# shrg-001.net
KiCad netlist of a schematic drawn in EAGLE
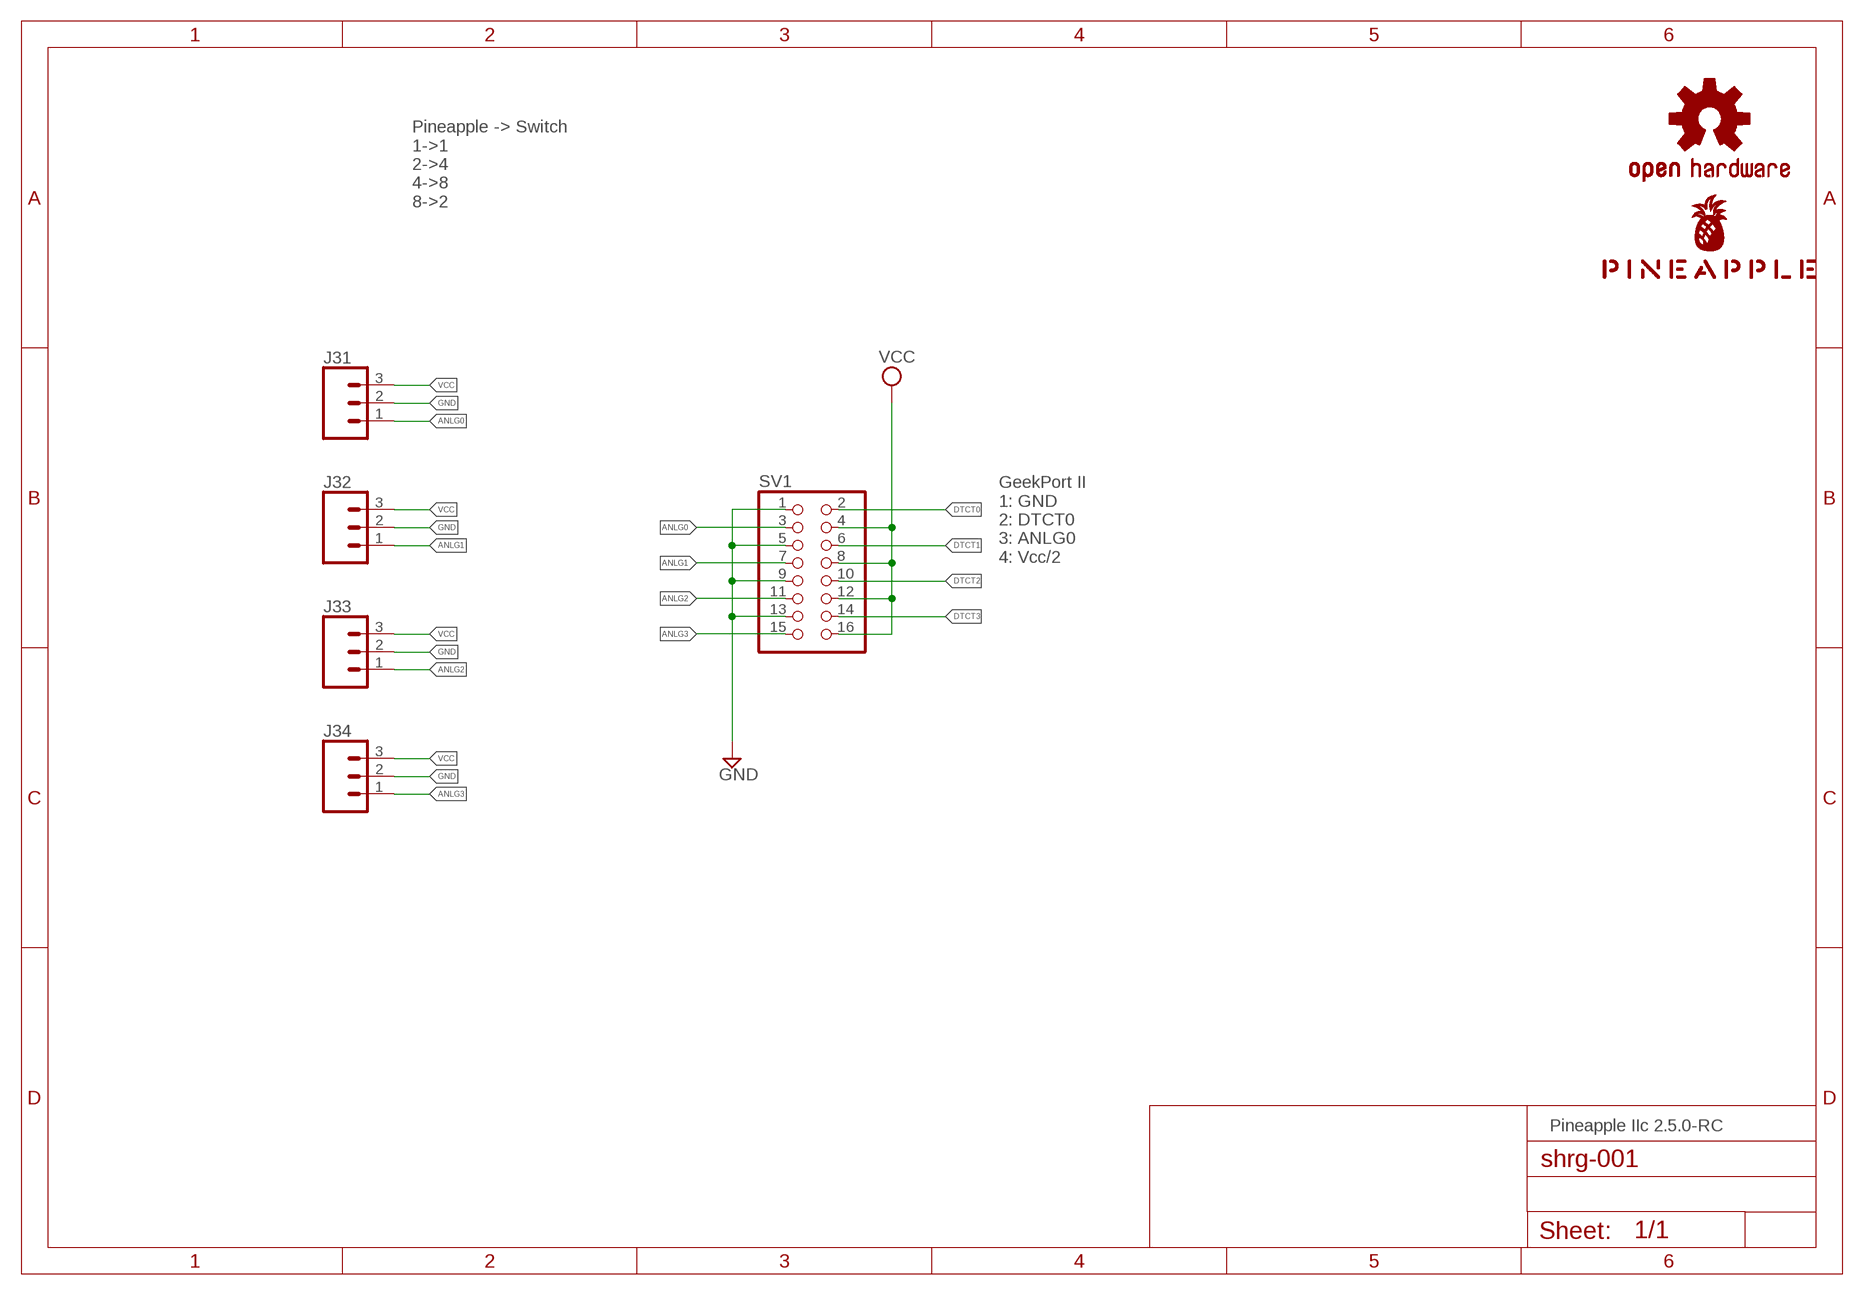
[diagram p0: schematic, sheet 1]

(export (version "E")
  (design (tool "Eeschema 10.0.6"))
  (components
    (comp (ref "J31")
      (value "CONN_03JST-PTH-VERT")
      (footprint "eagle-import:JST-3-PTH-VERT")
      (libsource (lib "eagle-import") (part "CONN_03JST-PTH-VERT"))
    )
    (comp (ref "J32")
      (value "CONN_03JST-PTH-VERT")
      (footprint "eagle-import:JST-3-PTH-VERT")
      (libsource (lib "eagle-import") (part "CONN_03JST-PTH-VERT"))
    )
    (comp (ref "J33")
      (value "CONN_03JST-PTH-VERT")
      (footprint "eagle-import:JST-3-PTH-VERT")
      (libsource (lib "eagle-import") (part "CONN_03JST-PTH-VERT"))
    )
    (comp (ref "J34")
      (value "CONN_03JST-PTH-VERT")
      (footprint "eagle-import:JST-3-PTH-VERT")
      (libsource (lib "eagle-import") (part "CONN_03JST-PTH-VERT"))
    )
    (comp (ref "LOGO1")
      (value "OSHW-LOGOS-COPPER")
      (footprint "eagle-import:OSHW-LOGO-S_COPPER")
      (libsource (lib "eagle-import") (part "OSHW-LOGOS-COPPER"))
    )
    (comp (ref "SV1")
      (value "PINHD-2X8")
      (footprint "eagle-import:2X08")
      (libsource (lib "eagle-import") (part "PINHD-2X8"))
    )
    (comp (ref "U$1")
      (value "PINEAPPLE450_SILK")
      (footprint "eagle-import:PINEAPPLE450_SILK")
      (libsource (lib "eagle-import") (part "PINEAPPLE450_SILK"))
    )
  )
  (nets
    (net (code "1") (name "ANLG0") (class "Default")
      (node (ref "J31") (pin "1") (pinfunction "1_1") (pintype "passive"))
      (node (ref "SV1") (pin "3") (pinfunction "3_3") (pintype "passive"))
    )
    (net (code "2") (name "ANLG1") (class "Default")
      (node (ref "J32") (pin "1") (pinfunction "1_1") (pintype "passive"))
      (node (ref "SV1") (pin "7") (pinfunction "7_7") (pintype "passive"))
    )
    (net (code "3") (name "ANLG2") (class "Default")
      (node (ref "J33") (pin "1") (pinfunction "1_1") (pintype "passive"))
      (node (ref "SV1") (pin "11") (pinfunction "11_11") (pintype "passive"))
    )
    (net (code "4") (name "ANLG3") (class "Default")
      (node (ref "J34") (pin "1") (pinfunction "1_1") (pintype "passive"))
      (node (ref "SV1") (pin "15") (pinfunction "15_15") (pintype "passive"))
    )
    (net (code "5") (name "DTCT0") (class "Default")
      (node (ref "SV1") (pin "2") (pinfunction "2_2") (pintype "passive"))
    )
    (net (code "6") (name "DTCT1") (class "Default")
      (node (ref "SV1") (pin "6") (pinfunction "6_6") (pintype "passive"))
    )
    (net (code "7") (name "DTCT2") (class "Default")
      (node (ref "SV1") (pin "10") (pinfunction "10_10") (pintype "passive"))
    )
    (net (code "8") (name "DTCT3") (class "Default")
      (node (ref "SV1") (pin "14") (pinfunction "14_14") (pintype "passive"))
    )
    (net (code "9") (name "GND") (class "Default")
      (node (ref "J31") (pin "2") (pinfunction "2_2") (pintype "passive"))
      (node (ref "J32") (pin "2") (pinfunction "2_2") (pintype "passive"))
      (node (ref "J33") (pin "2") (pinfunction "2_2") (pintype "passive"))
      (node (ref "J34") (pin "2") (pinfunction "2_2") (pintype "passive"))
      (node (ref "SV1") (pin "1") (pinfunction "1_1") (pintype "passive"))
      (node (ref "SV1") (pin "13") (pinfunction "13_13") (pintype "passive"))
      (node (ref "SV1") (pin "5") (pinfunction "5_5") (pintype "passive"))
      (node (ref "SV1") (pin "9") (pinfunction "9_9") (pintype "passive"))
    )
    (net (code "10") (name "VCC") (class "Default")
      (node (ref "J31") (pin "3") (pinfunction "3_3") (pintype "passive"))
      (node (ref "J32") (pin "3") (pinfunction "3_3") (pintype "passive"))
      (node (ref "J33") (pin "3") (pinfunction "3_3") (pintype "passive"))
      (node (ref "J34") (pin "3") (pinfunction "3_3") (pintype "passive"))
      (node (ref "SV1") (pin "12") (pinfunction "12_12") (pintype "passive"))
      (node (ref "SV1") (pin "16") (pinfunction "16_16") (pintype "passive"))
      (node (ref "SV1") (pin "4") (pinfunction "4_4") (pintype "passive"))
      (node (ref "SV1") (pin "8") (pinfunction "8_8") (pintype "passive"))
    )
  )
)
